# PHOTODIODE.net
KiCad netlist of a schematic drawn in Altium Designer
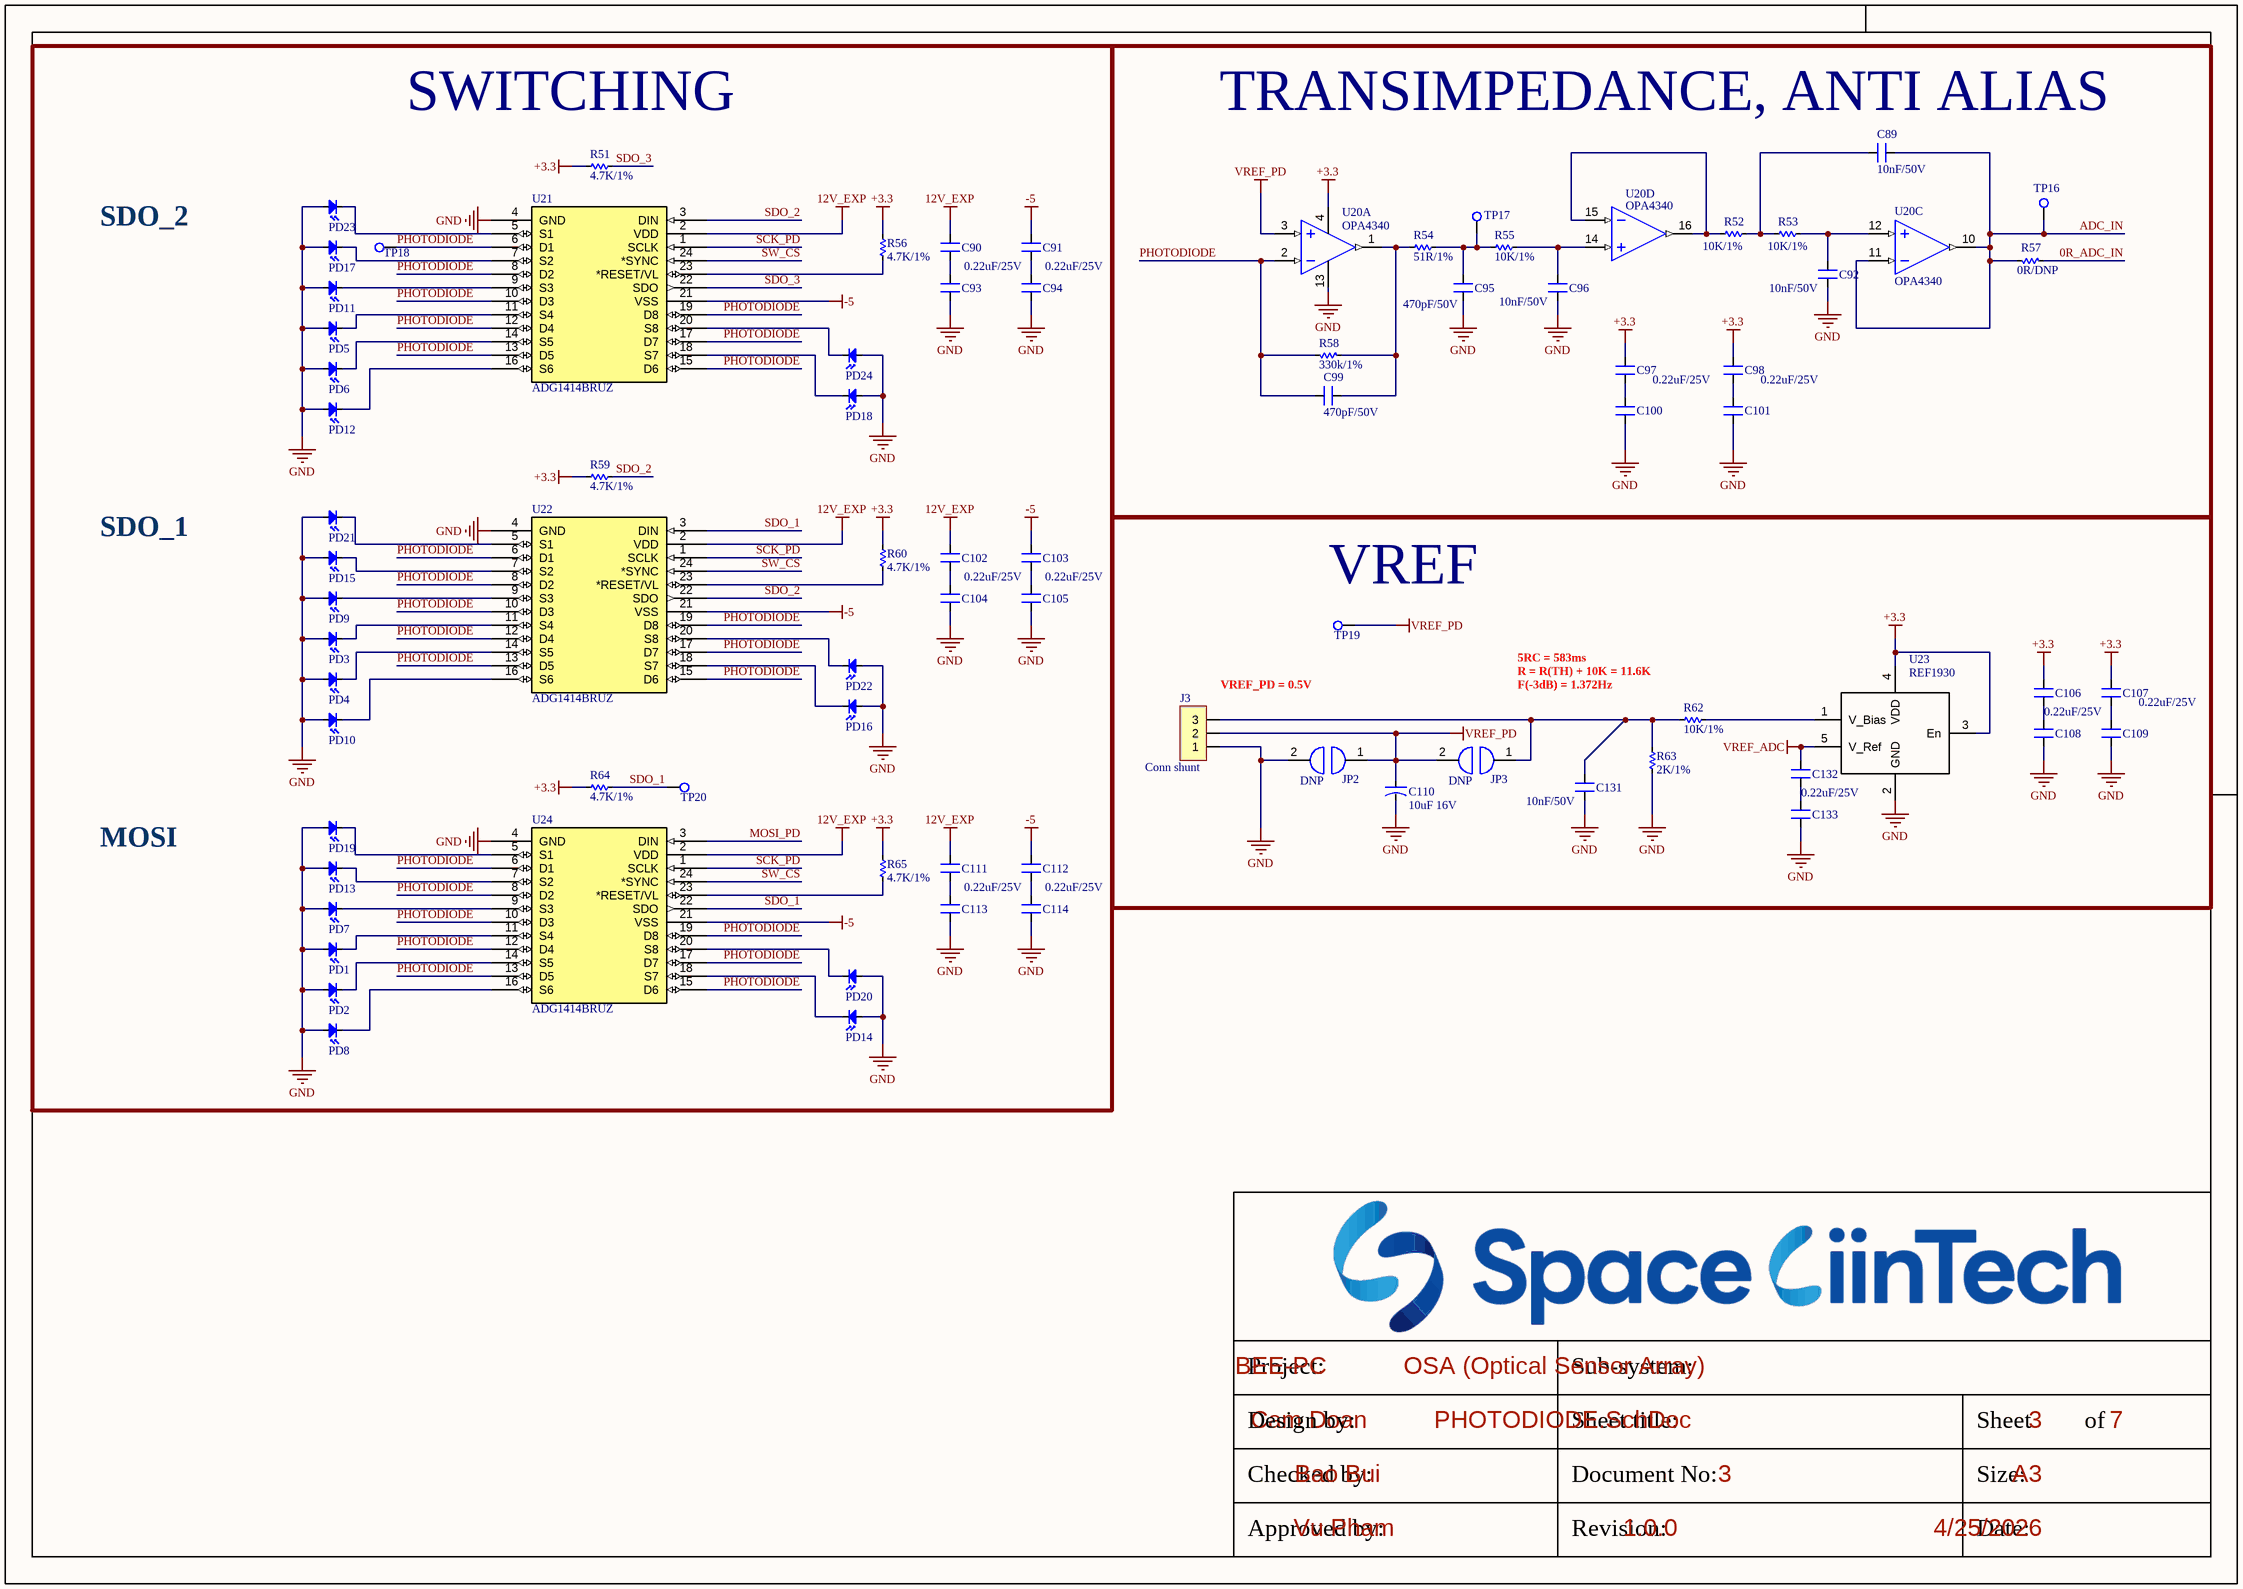
[diagram p0: PHOTODIODE.SchDoc]

(export (version "E")
  (design (tool "Eeschema 10.0.6"))
  (components
    (comp (ref "C89")
      (value "10nF/50V")
      (footprint "CN-SMD-0603")
      (description "CL10B103KB8NNNC")
      (libsource (lib "Capacitors") (part "CM"))
    )
    (comp (ref "C90")
      (value "0.22uF/25V")
      (footprint "CN-SMD-0603")
      (description "CL10B224KA8NNNC")
      (libsource (lib "Capacitors") (part "CM"))
    )
    (comp (ref "C91")
      (value "0.22uF/25V")
      (footprint "CN-SMD-0603")
      (description "CL10B224KA8NNNC")
      (libsource (lib "Capacitors") (part "CM"))
    )
    (comp (ref "C92")
      (value "10nF/50V")
      (footprint "CN-SMD-0603")
      (description "CL10B103KB8NNNC")
      (libsource (lib "Capacitors") (part "CM"))
    )
    (comp (ref "C93")
      (value "0.22uF/25V")
      (footprint "CN-SMD-0603")
      (description "CL10B224KA8NNNC")
      (libsource (lib "Capacitors") (part "CM"))
    )
    (comp (ref "C94")
      (value "0.22uF/25V")
      (footprint "CN-SMD-0603")
      (description "CL10B224KA8NNNC")
      (libsource (lib "Capacitors") (part "CM"))
    )
    (comp (ref "C95")
      (value "470pF/50V")
      (footprint "CN-SMD-0603")
      (description "CL10B471KB8NNNC")
      (libsource (lib "Capacitors") (part "CM"))
    )
    (comp (ref "C96")
      (value "10nF/50V")
      (footprint "CN-SMD-0603")
      (description "CL10B103KB8NNNC")
      (libsource (lib "Capacitors") (part "CM"))
    )
    (comp (ref "C97")
      (value "0.22uF/25V")
      (footprint "CN-SMD-0603")
      (description "CL10B224KA8NNNC")
      (libsource (lib "Capacitors") (part "CM"))
    )
    (comp (ref "C98")
      (value "0.22uF/25V")
      (footprint "CN-SMD-0603")
      (description "CL10B224KA8NNNC")
      (libsource (lib "Capacitors") (part "CM"))
    )
    (comp (ref "C99")
      (value "470pF/50V")
      (footprint "CN-SMD-0603")
      (description "CL10B471KB8NNNC")
      (libsource (lib "Capacitors") (part "CM"))
    )
    (comp (ref "C100")
      (value "0.22uF/25V")
      (footprint "CN-SMD-0603")
      (description "CL10B224KA8NNNC")
      (libsource (lib "Capacitors") (part "CM"))
    )
    (comp (ref "C101")
      (value "0.22uF/25V")
      (footprint "CN-SMD-0603")
      (description "CL10B224KA8NNNC")
      (libsource (lib "Capacitors") (part "CM"))
    )
    (comp (ref "C102")
      (value "0.22uF/25V")
      (footprint "CN-SMD-0603")
      (description "CL10B224KA8NNNC")
      (libsource (lib "Capacitors") (part "CM"))
    )
    (comp (ref "C103")
      (value "0.22uF/25V")
      (footprint "CN-SMD-0603")
      (description "CL10B224KA8NNNC")
      (libsource (lib "Capacitors") (part "CM"))
    )
    (comp (ref "C104")
      (value "0.22uF/25V")
      (footprint "CN-SMD-0603")
      (description "CL10B224KA8NNNC")
      (libsource (lib "Capacitors") (part "CM"))
    )
    (comp (ref "C105")
      (value "0.22uF/25V")
      (footprint "CN-SMD-0603")
      (description "CL10B224KA8NNNC")
      (libsource (lib "Capacitors") (part "CM"))
    )
    (comp (ref "C106")
      (value "0.22uF/25V")
      (footprint "CN-SMD-0603")
      (description "CL10B224KA8NNNC")
      (libsource (lib "Capacitors") (part "CM"))
    )
    (comp (ref "C107")
      (value "0.22uF/25V")
      (footprint "CN-SMD-0603")
      (description "CL10B224KA8NNNC")
      (libsource (lib "Capacitors") (part "CM"))
    )
    (comp (ref "C108")
      (value "0.22uF/25V")
      (footprint "CN-SMD-0603")
      (description "CL10B224KA8NNNC")
      (libsource (lib "Capacitors") (part "CM"))
    )
    (comp (ref "C109")
      (value "0.22uF/25V")
      (footprint "CN-SMD-0603")
      (description "CL10B224KA8NNNC")
      (libsource (lib "Capacitors") (part "CM"))
    )
    (comp (ref "C110")
      (value "10uF 16V")
      (footprint "CAP_TANT_1206")
      (description "TAJA106K016RNJ")
      (fields (field (name "PUBLISHER") "Altium Limited"))
      (libsource (lib "Library_HUNG") (part "CN-ALU-SMD"))
    )
    (comp (ref "C111")
      (value "0.22uF/25V")
      (footprint "CN-SMD-0603")
      (description "CL10B224KA8NNNC")
      (libsource (lib "Capacitors") (part "CM"))
    )
    (comp (ref "C112")
      (value "0.22uF/25V")
      (footprint "CN-SMD-0603")
      (description "CL10B224KA8NNNC")
      (libsource (lib "Capacitors") (part "CM"))
    )
    (comp (ref "C113")
      (value "0.22uF/25V")
      (footprint "CN-SMD-0603")
      (description "CL10B224KA8NNNC")
      (libsource (lib "Capacitors") (part "CM"))
    )
    (comp (ref "C114")
      (value "0.22uF/25V")
      (footprint "CN-SMD-0603")
      (description "CL10B224KA8NNNC")
      (libsource (lib "Capacitors") (part "CM"))
    )
    (comp (ref "C131")
      (value "10nF/50V")
      (footprint "CN-SMD-0603")
      (description "CL10B103KB8NNNC")
      (libsource (lib "Capacitors") (part "CM"))
    )
    (comp (ref "C132")
      (value "0.22uF/25V")
      (footprint "CN-SMD-0603")
      (description "CL10B224KA8NNNC")
      (libsource (lib "Capacitors") (part "CM"))
    )
    (comp (ref "C133")
      (value "0.22uF/25V")
      (footprint "CN-SMD-0603")
      (description "CL10B224KA8NNNC")
      (libsource (lib "Capacitors") (part "CM"))
    )
    (comp (ref "J3")
      (value "Conn shunt")
      (footprint "M50-3930342")
      (description "WR-PHD 2.54 mm Angled Socket Header")
      (fields
        (field (name "MANUFACTURER") "Würth Elektronik eiSos GmbH")
        (field (name "PARTNO") "613003143121")
        (field (name "CREATED BY") "Karrer Zheng")
      )
      (libsource (lib "Library") (part "JP3"))
    )
    (comp (ref "JP2") (value "DNP") (footprint "JUMPER_1608") (libsource (lib "EXP_V1") (part "JUMPER")))
    (comp (ref "JP3") (value "DNP") (footprint "JUMPER_1608") (libsource (lib "EXP_V1") (part "JUMPER")))
    (comp (ref "PD1")
      (value "Photodiode")
      (footprint "VEMD5080X01")
      (description "VEMD5080X01")
      (libsource (lib "Library_HUNG") (part "Photodiode"))
    )
    (comp (ref "PD2")
      (value "Photodiode")
      (footprint "VEMD5080X01")
      (description "VEMD5080X01")
      (libsource (lib "Library_HUNG") (part "Photodiode"))
    )
    (comp (ref "PD3")
      (value "Photodiode")
      (footprint "VEMD5080X01")
      (description "VEMD5080X01")
      (libsource (lib "Library_HUNG") (part "Photodiode"))
    )
    (comp (ref "PD4")
      (value "Photodiode")
      (footprint "VEMD5080X01")
      (description "VEMD5080X01")
      (libsource (lib "Library_HUNG") (part "Photodiode"))
    )
    (comp (ref "PD5")
      (value "Photodiode")
      (footprint "VEMD5080X01")
      (description "VEMD5080X01")
      (libsource (lib "Library_HUNG") (part "Photodiode"))
    )
    (comp (ref "PD6")
      (value "Photodiode")
      (footprint "VEMD5080X01")
      (description "VEMD5080X01")
      (libsource (lib "Library_HUNG") (part "Photodiode"))
    )
    (comp (ref "PD7")
      (value "Photodiode")
      (footprint "VEMD5080X01")
      (description "VEMD5080X01")
      (libsource (lib "Library_HUNG") (part "Photodiode"))
    )
    (comp (ref "PD8")
      (value "Photodiode")
      (footprint "VEMD5080X01")
      (description "VEMD5080X01")
      (libsource (lib "Library_HUNG") (part "Photodiode"))
    )
    (comp (ref "PD9")
      (value "Photodiode")
      (footprint "VEMD5080X01")
      (description "VEMD5080X01")
      (libsource (lib "Library_HUNG") (part "Photodiode"))
    )
    (comp (ref "PD10")
      (value "Photodiode")
      (footprint "VEMD5080X01")
      (description "VEMD5080X01")
      (libsource (lib "Library_HUNG") (part "Photodiode"))
    )
    (comp (ref "PD11")
      (value "Photodiode")
      (footprint "VEMD5080X01")
      (description "VEMD5080X01")
      (libsource (lib "Library_HUNG") (part "Photodiode"))
    )
    (comp (ref "PD12")
      (value "Photodiode")
      (footprint "VEMD5080X01")
      (description "VEMD5080X01")
      (libsource (lib "Library_HUNG") (part "Photodiode"))
    )
    (comp (ref "PD13")
      (value "Photodiode")
      (footprint "VEMD5080X01")
      (description "VEMD5080X01")
      (libsource (lib "Library_HUNG") (part "Photodiode"))
    )
    (comp (ref "PD14")
      (value "Photodiode")
      (footprint "VEMD5080X01")
      (description "VEMD5080X01")
      (libsource (lib "Library_HUNG") (part "Photodiode"))
    )
    (comp (ref "PD15")
      (value "Photodiode")
      (footprint "VEMD5080X01")
      (description "VEMD5080X01")
      (libsource (lib "Library_HUNG") (part "Photodiode"))
    )
    (comp (ref "PD16")
      (value "Photodiode")
      (footprint "VEMD5080X01")
      (description "VEMD5080X01")
      (libsource (lib "Library_HUNG") (part "Photodiode"))
    )
    (comp (ref "PD17")
      (value "Photodiode")
      (footprint "VEMD5080X01")
      (description "VEMD5080X01")
      (libsource (lib "Library_HUNG") (part "Photodiode"))
    )
    (comp (ref "PD18")
      (value "Photodiode")
      (footprint "VEMD5080X01")
      (description "VEMD5080X01")
      (libsource (lib "Library_HUNG") (part "Photodiode"))
    )
    (comp (ref "PD19")
      (value "Photodiode")
      (footprint "VEMD5080X01")
      (description "VEMD5080X01")
      (libsource (lib "Library_HUNG") (part "Photodiode"))
    )
    (comp (ref "PD20")
      (value "Photodiode")
      (footprint "VEMD5080X01")
      (description "VEMD5080X01")
      (libsource (lib "Library_HUNG") (part "Photodiode"))
    )
    (comp (ref "PD21")
      (value "Photodiode")
      (footprint "VEMD5080X01")
      (description "VEMD5080X01")
      (libsource (lib "Library_HUNG") (part "Photodiode"))
    )
    (comp (ref "PD22")
      (value "Photodiode")
      (footprint "VEMD5080X01")
      (description "VEMD5080X01")
      (libsource (lib "Library_HUNG") (part "Photodiode"))
    )
    (comp (ref "PD23")
      (value "Photodiode")
      (footprint "VEMD5080X01")
      (description "VEMD5080X01")
      (libsource (lib "Library_HUNG") (part "Photodiode"))
    )
    (comp (ref "PD24")
      (value "Photodiode")
      (footprint "VEMD5080X01")
      (description "VEMD5080X01")
      (libsource (lib "Library_HUNG") (part "Photodiode"))
    )
    (comp (ref "R51")
      (value "4.7K/1%")
      (footprint "RES-SMD-0603")
      (description "ERJ-3EKF4701V")
      (fields
        (field (name "MANUFACTURER") "Generic Components")
        (field (name "PUBLISHER") "Altium Hobart Technology Centre")
      )
      (libsource (lib "Library") (part "Res-SMD"))
    )
    (comp (ref "R52")
      (value "10K/1%")
      (footprint "RES-SMD-0603")
      (description "ERJ-3EKF1002V")
      (fields
        (field (name "MANUFACTURER") "Generic Components")
        (field (name "PUBLISHER") "Altium Hobart Technology Centre")
      )
      (libsource (lib "Library") (part "Res-SMD"))
    )
    (comp (ref "R53")
      (value "10K/1%")
      (footprint "RES-SMD-0603")
      (description "ERJ-3EKF1002V")
      (fields
        (field (name "MANUFACTURER") "Generic Components")
        (field (name "PUBLISHER") "Altium Hobart Technology Centre")
      )
      (libsource (lib "Library") (part "Res-SMD"))
    )
    (comp (ref "R54")
      (value "51R/1%")
      (footprint "RES-SMD-0603")
      (description "ERJ-3EKF51R0V")
      (fields
        (field (name "MANUFACTURER") "Generic Components")
        (field (name "PUBLISHER") "Altium Hobart Technology Centre")
      )
      (libsource (lib "Library") (part "Res-SMD"))
    )
    (comp (ref "R55")
      (value "10K/1%")
      (footprint "RES-SMD-0603")
      (description "ERJ-3EKF1002V")
      (fields
        (field (name "MANUFACTURER") "Generic Components")
        (field (name "PUBLISHER") "Altium Hobart Technology Centre")
      )
      (libsource (lib "Library") (part "Res-SMD"))
    )
    (comp (ref "R56")
      (value "4.7K/1%")
      (footprint "RES-SMD-0603")
      (description "ERJ-3EKF4701V")
      (fields
        (field (name "MANUFACTURER") "Generic Components")
        (field (name "PUBLISHER") "Altium Hobart Technology Centre")
      )
      (libsource (lib "Library") (part "Res-SMD"))
    )
    (comp (ref "R57")
      (value "0R/DNP")
      (footprint "RES-SMD-0603")
      (description "ERJ-3GEY0R00V")
      (fields
        (field (name "MANUFACTURER") "Generic Components")
        (field (name "PUBLISHER") "Altium Hobart Technology Centre")
      )
      (libsource (lib "Library") (part "Res-SMD"))
    )
    (comp (ref "R58")
      (value "330k/1%")
      (footprint "RES-SMD-0603")
      (description "ERJ-3EKF3303V")
      (fields
        (field (name "MANUFACTURER") "Generic Components")
        (field (name "PUBLISHER") "Altium Hobart Technology Centre")
      )
      (libsource (lib "Library") (part "Res-SMD"))
    )
    (comp (ref "R59")
      (value "4.7K/1%")
      (footprint "RES-SMD-0603")
      (description "ERJ-3EKF4701V")
      (fields
        (field (name "MANUFACTURER") "Generic Components")
        (field (name "PUBLISHER") "Altium Hobart Technology Centre")
      )
      (libsource (lib "Library") (part "Res-SMD"))
    )
    (comp (ref "R60")
      (value "4.7K/1%")
      (footprint "RES-SMD-0603")
      (description "ERJ-3EKF4701V")
      (fields
        (field (name "MANUFACTURER") "Generic Components")
        (field (name "PUBLISHER") "Altium Hobart Technology Centre")
      )
      (libsource (lib "Library") (part "Res-SMD"))
    )
    (comp (ref "R62")
      (value "10K/1%")
      (footprint "RES-SMD-0603")
      (description "ERJ-3EKF1002V")
      (fields
        (field (name "MANUFACTURER") "Generic Components")
        (field (name "PUBLISHER") "Altium Hobart Technology Centre")
      )
      (libsource (lib "Library") (part "Res-SMD"))
    )
    (comp (ref "R63")
      (value "2K/1%")
      (footprint "RES-SMD-0603")
      (description "ERJ-3EKF2001V")
      (fields
        (field (name "MANUFACTURER") "Generic Components")
        (field (name "PUBLISHER") "Altium Hobart Technology Centre")
      )
      (libsource (lib "Library") (part "Res-SMD"))
    )
    (comp (ref "R64")
      (value "4.7K/1%")
      (footprint "RES-SMD-0603")
      (description "ERJ-3EKF4701V")
      (fields
        (field (name "MANUFACTURER") "Generic Components")
        (field (name "PUBLISHER") "Altium Hobart Technology Centre")
      )
      (libsource (lib "Library") (part "Res-SMD"))
    )
    (comp (ref "R65")
      (value "4.7K/1%")
      (footprint "RES-SMD-0603")
      (description "ERJ-3EKF4701V")
      (fields
        (field (name "MANUFACTURER") "Generic Components")
        (field (name "PUBLISHER") "Altium Hobart Technology Centre")
      )
      (libsource (lib "Library") (part "Res-SMD"))
    )
    (comp (ref "TP16")
      (value "Test_Point")
      (footprint "TESTPOINT")
      (libsource (lib "Library_HUNG") (part "Test_Point"))
    )
    (comp (ref "TP17")
      (value "Test_Point")
      (footprint "TESTPOINT")
      (libsource (lib "Library_HUNG") (part "Test_Point"))
    )
    (comp (ref "TP18")
      (value "Test_Point")
      (footprint "TESTPOINT")
      (libsource (lib "Library_HUNG") (part "Test_Point"))
    )
    (comp (ref "TP19")
      (value "Test_Point")
      (footprint "TESTPOINT")
      (libsource (lib "Library_HUNG") (part "Test_Point"))
    )
    (comp (ref "TP20")
      (value "Test_Point")
      (footprint "TESTPOINT")
      (libsource (lib "Library_HUNG") (part "Test_Point"))
    )
    (comp (ref "U20")
      (value "OPA4340")
      (footprint "SSOP16")
      (description "OPA4340UA/2K5")
      (libsource (lib "Library") (part "OPA4340"))
    )
    (comp (ref "U21")
      (value "ADG1414BRUZ")
      (footprint "TSSOP24")
      (libsource (lib "Library_HUNG") (part "ADG1414BRUZ"))
    )
    (comp (ref "U22")
      (value "ADG1414BRUZ")
      (footprint "TSSOP24")
      (libsource (lib "Library_HUNG") (part "ADG1414BRUZ"))
    )
    (comp (ref "U23")
      (value "REF1930")
      (footprint "SOT23-5")
      (description "REF1941AIDDCT")
      (libsource (lib "Library") (part "REF19xx"))
    )
    (comp (ref "U24")
      (value "ADG1414BRUZ")
      (footprint "TSSOP24")
      (libsource (lib "Library_HUNG") (part "ADG1414BRUZ"))
    )
  )
  (nets
    (net (code "1") (name "+3.3") (class "Default")
      (node (ref "C106") (pin "2") (pinfunction "2_2") (pintype "passive"))
      (node (ref "C107") (pin "2") (pinfunction "2_2") (pintype "passive"))
      (node (ref "C97") (pin "2") (pinfunction "2_2") (pintype "passive"))
      (node (ref "C98") (pin "2") (pinfunction "2_2") (pintype "passive"))
      (node (ref "R51") (pin "2") (pinfunction "2_2") (pintype "passive"))
      (node (ref "R56") (pin "2") (pinfunction "2_2") (pintype "passive"))
      (node (ref "R59") (pin "2") (pinfunction "2_2") (pintype "passive"))
      (node (ref "R60") (pin "2") (pinfunction "2_2") (pintype "passive"))
      (node (ref "R64") (pin "2") (pinfunction "2_2") (pintype "passive"))
      (node (ref "R65") (pin "2") (pinfunction "2_2") (pintype "passive"))
      (node (ref "U20") (pin "4") (pinfunction "+V_4") (pintype "passive"))
      (node (ref "U23") (pin "3") (pinfunction "En_3") (pintype "passive"))
      (node (ref "U23") (pin "4") (pinfunction "VDD_4") (pintype "passive"))
    )
    (net (code "2") (name "-5") (class "Default")
      (node (ref "C103") (pin "2") (pinfunction "2_2") (pintype "passive"))
      (node (ref "C112") (pin "2") (pinfunction "2_2") (pintype "passive"))
      (node (ref "C91") (pin "2") (pinfunction "2_2") (pintype "passive"))
      (node (ref "U21") (pin "21") (pinfunction "VSS_21") (pintype "power_in"))
      (node (ref "U22") (pin "21") (pinfunction "VSS_21") (pintype "power_in"))
      (node (ref "U24") (pin "21") (pinfunction "VSS_21") (pintype "power_in"))
    )
    (net (code "3") (name "/0R_ADC_IN") (class "Default")
      (node (ref "R57") (pin "1") (pinfunction "1_1") (pintype "passive"))
    )
    (net (code "4") (name "/ADC_IN") (class "Default")
      (node (ref "C89") (pin "1") (pinfunction "1_1") (pintype "passive"))
      (node (ref "R57") (pin "2") (pinfunction "2_2") (pintype "passive"))
      (node (ref "TP16") (pin "1") (pintype "power_in"))
      (node (ref "U20") (pin "10") (pinfunction "OUT_10") (pintype "output"))
      (node (ref "U20") (pin "11") (pinfunction "IN-_11") (pintype "input"))
    )
    (net (code "5") (name "/MOSI_PD") (class "Default")
      (node (ref "U24") (pin "3") (pinfunction "DIN_3") (pintype "input"))
    )
    (net (code "6") (name "/PHOTODIODE") (class "Default")
      (node (ref "C99") (pin "1") (pinfunction "1_1") (pintype "passive"))
      (node (ref "R58") (pin "1") (pinfunction "1_1") (pintype "passive"))
      (node (ref "TP18") (pin "1") (pintype "power_in"))
      (node (ref "U20") (pin "2") (pinfunction "IN-_2") (pintype "input"))
      (node (ref "U21") (pin "10") (pinfunction "D3_10") (pintype "bidirectional"))
      (node (ref "U21") (pin "12") (pinfunction "D4_12") (pintype "bidirectional"))
      (node (ref "U21") (pin "13") (pinfunction "D5_13") (pintype "bidirectional"))
      (node (ref "U21") (pin "15") (pinfunction "D6_15") (pintype "bidirectional"))
      (node (ref "U21") (pin "17") (pinfunction "D7_17") (pintype "bidirectional"))
      (node (ref "U21") (pin "19") (pinfunction "D8_19") (pintype "bidirectional"))
      (node (ref "U21") (pin "6") (pinfunction "D1_6") (pintype "bidirectional"))
      (node (ref "U21") (pin "8") (pinfunction "D2_8") (pintype "bidirectional"))
      (node (ref "U22") (pin "10") (pinfunction "D3_10") (pintype "bidirectional"))
      (node (ref "U22") (pin "12") (pinfunction "D4_12") (pintype "bidirectional"))
      (node (ref "U22") (pin "13") (pinfunction "D5_13") (pintype "bidirectional"))
      (node (ref "U22") (pin "15") (pinfunction "D6_15") (pintype "bidirectional"))
      (node (ref "U22") (pin "17") (pinfunction "D7_17") (pintype "bidirectional"))
      (node (ref "U22") (pin "19") (pinfunction "D8_19") (pintype "bidirectional"))
      (node (ref "U22") (pin "6") (pinfunction "D1_6") (pintype "bidirectional"))
      (node (ref "U22") (pin "8") (pinfunction "D2_8") (pintype "bidirectional"))
      (node (ref "U24") (pin "10") (pinfunction "D3_10") (pintype "bidirectional"))
      (node (ref "U24") (pin "12") (pinfunction "D4_12") (pintype "bidirectional"))
      (node (ref "U24") (pin "13") (pinfunction "D5_13") (pintype "bidirectional"))
      (node (ref "U24") (pin "15") (pinfunction "D6_15") (pintype "bidirectional"))
      (node (ref "U24") (pin "17") (pinfunction "D7_17") (pintype "bidirectional"))
      (node (ref "U24") (pin "19") (pinfunction "D8_19") (pintype "bidirectional"))
      (node (ref "U24") (pin "6") (pinfunction "D1_6") (pintype "bidirectional"))
      (node (ref "U24") (pin "8") (pinfunction "D2_8") (pintype "bidirectional"))
    )
    (net (code "7") (name "/SCK_PD") (class "Default")
      (node (ref "U21") (pin "1") (pinfunction "SCLK_1") (pintype "input"))
      (node (ref "U22") (pin "1") (pinfunction "SCLK_1") (pintype "input"))
      (node (ref "U24") (pin "1") (pinfunction "SCLK_1") (pintype "input"))
    )
    (net (code "8") (name "/SDO_1") (class "Default")
      (node (ref "R64") (pin "1") (pinfunction "1_1") (pintype "passive"))
      (node (ref "TP20") (pin "1") (pintype "power_in"))
      (node (ref "U22") (pin "3") (pinfunction "DIN_3") (pintype "input"))
      (node (ref "U24") (pin "22") (pinfunction "SDO_22") (pintype "output"))
    )
    (net (code "9") (name "/SDO_2") (class "Default")
      (node (ref "R59") (pin "1") (pinfunction "1_1") (pintype "passive"))
      (node (ref "U21") (pin "3") (pinfunction "DIN_3") (pintype "input"))
      (node (ref "U22") (pin "22") (pinfunction "SDO_22") (pintype "output"))
    )
    (net (code "10") (name "/SDO_3") (class "Default")
      (node (ref "R51") (pin "1") (pinfunction "1_1") (pintype "passive"))
      (node (ref "U21") (pin "22") (pinfunction "SDO_22") (pintype "output"))
    )
    (net (code "11") (name "/SW_CS") (class "Default")
      (node (ref "U21") (pin "24") (pinfunction "*SYNC_24") (pintype "input"))
      (node (ref "U22") (pin "24") (pinfunction "*SYNC_24") (pintype "input"))
      (node (ref "U24") (pin "24") (pinfunction "*SYNC_24") (pintype "input"))
    )
    (net (code "12") (name "12V_EXP") (class "Default")
      (node (ref "C102") (pin "2") (pinfunction "2_2") (pintype "passive"))
      (node (ref "C111") (pin "2") (pinfunction "2_2") (pintype "passive"))
      (node (ref "C90") (pin "2") (pinfunction "2_2") (pintype "passive"))
      (node (ref "U21") (pin "2") (pinfunction "VDD_2") (pintype "power_in"))
      (node (ref "U22") (pin "2") (pinfunction "VDD_2") (pintype "power_in"))
      (node (ref "U24") (pin "2") (pinfunction "VDD_2") (pintype "power_in"))
    )
    (net (code "13") (name "GND") (class "Default")
      (node (ref "C100") (pin "1") (pinfunction "1_1") (pintype "passive"))
      (node (ref "C101") (pin "1") (pinfunction "1_1") (pintype "passive"))
      (node (ref "C104") (pin "1") (pinfunction "1_1") (pintype "passive"))
      (node (ref "C105") (pin "1") (pinfunction "1_1") (pintype "passive"))
      (node (ref "C108") (pin "1") (pinfunction "1_1") (pintype "passive"))
      (node (ref "C109") (pin "1") (pinfunction "1_1") (pintype "passive"))
      (node (ref "C110") (pin "2") (pinfunction "2_2") (pintype "passive"))
      (node (ref "C113") (pin "1") (pinfunction "1_1") (pintype "passive"))
      (node (ref "C114") (pin "1") (pinfunction "1_1") (pintype "passive"))
      (node (ref "C131") (pin "1") (pinfunction "1_1") (pintype "passive"))
      (node (ref "C133") (pin "1") (pinfunction "1_1") (pintype "passive"))
      (node (ref "C92") (pin "1") (pinfunction "1_1") (pintype "passive"))
      (node (ref "C93") (pin "1") (pinfunction "1_1") (pintype "passive"))
      (node (ref "C94") (pin "1") (pinfunction "1_1") (pintype "passive"))
      (node (ref "C95") (pin "1") (pinfunction "1_1") (pintype "passive"))
      (node (ref "C96") (pin "1") (pinfunction "1_1") (pintype "passive"))
      (node (ref "J3") (pin "1") (pinfunction "1_1") (pintype "passive"))
      (node (ref "JP2") (pin "2") (pinfunction "2_2") (pintype "passive"))
      (node (ref "PD1") (pin "1") (pinfunction "A_1") (pintype "passive"))
      (node (ref "PD10") (pin "1") (pinfunction "A_1") (pintype "passive"))
      (node (ref "PD11") (pin "1") (pinfunction "A_1") (pintype "passive"))
      (node (ref "PD12") (pin "1") (pinfunction "A_1") (pintype "passive"))
      (node (ref "PD13") (pin "1") (pinfunction "A_1") (pintype "passive"))
      (node (ref "PD14") (pin "1") (pinfunction "A_1") (pintype "passive"))
      (node (ref "PD15") (pin "1") (pinfunction "A_1") (pintype "passive"))
      (node (ref "PD16") (pin "1") (pinfunction "A_1") (pintype "passive"))
      (node (ref "PD17") (pin "1") (pinfunction "A_1") (pintype "passive"))
      (node (ref "PD18") (pin "1") (pinfunction "A_1") (pintype "passive"))
      (node (ref "PD19") (pin "1") (pinfunction "A_1") (pintype "passive"))
      (node (ref "PD2") (pin "1") (pinfunction "A_1") (pintype "passive"))
      (node (ref "PD20") (pin "1") (pinfunction "A_1") (pintype "passive"))
      (node (ref "PD21") (pin "1") (pinfunction "A_1") (pintype "passive"))
      (node (ref "PD22") (pin "1") (pinfunction "A_1") (pintype "passive"))
      (node (ref "PD23") (pin "1") (pinfunction "A_1") (pintype "passive"))
      (node (ref "PD24") (pin "1") (pinfunction "A_1") (pintype "passive"))
      (node (ref "PD3") (pin "1") (pinfunction "A_1") (pintype "passive"))
      (node (ref "PD4") (pin "1") (pinfunction "A_1") (pintype "passive"))
      (node (ref "PD5") (pin "1") (pinfunction "A_1") (pintype "passive"))
      (node (ref "PD6") (pin "1") (pinfunction "A_1") (pintype "passive"))
      (node (ref "PD7") (pin "1") (pinfunction "A_1") (pintype "passive"))
      (node (ref "PD8") (pin "1") (pinfunction "A_1") (pintype "passive"))
      (node (ref "PD9") (pin "1") (pinfunction "A_1") (pintype "passive"))
      (node (ref "R63") (pin "1") (pinfunction "1_1") (pintype "passive"))
      (node (ref "U20") (pin "13") (pinfunction "-V_13") (pintype "passive"))
      (node (ref "U21") (pin "4") (pinfunction "GND_4") (pintype "power_in"))
      (node (ref "U22") (pin "4") (pinfunction "GND_4") (pintype "power_in"))
      (node (ref "U23") (pin "2") (pinfunction "GND_2") (pintype "passive"))
      (node (ref "U24") (pin "4") (pinfunction "GND_4") (pintype "power_in"))
    )
    (net (code "14") (name "Net-(C89-Pad2)") (class "Default")
      (node (ref "C89") (pin "2") (pinfunction "2_2") (pintype "passive"))
      (node (ref "R52") (pin "2") (pinfunction "2_2") (pintype "passive"))
      (node (ref "R53") (pin "1") (pinfunction "1_1") (pintype "passive"))
    )
    (net (code "15") (name "Net-(C90-Pad1)") (class "Default")
      (node (ref "C90") (pin "1") (pinfunction "1_1") (pintype "passive"))
      (node (ref "C93") (pin "2") (pinfunction "2_2") (pintype "passive"))
    )
    (net (code "16") (name "Net-(C91-Pad1)") (class "Default")
      (node (ref "C91") (pin "1") (pinfunction "1_1") (pintype "passive"))
      (node (ref "C94") (pin "2") (pinfunction "2_2") (pintype "passive"))
    )
    (net (code "17") (name "Net-(C95-Pad2)") (class "Default")
      (node (ref "C95") (pin "2") (pinfunction "2_2") (pintype "passive"))
      (node (ref "R54") (pin "2") (pinfunction "2_2") (pintype "passive"))
      (node (ref "R55") (pin "1") (pinfunction "1_1") (pintype "passive"))
      (node (ref "TP17") (pin "1") (pintype "power_in"))
    )
    (net (code "18") (name "Net-(C100-Pad2)") (class "Default")
      (node (ref "C100") (pin "2") (pinfunction "2_2") (pintype "passive"))
      (node (ref "C97") (pin "1") (pinfunction "1_1") (pintype "passive"))
    )
    (net (code "19") (name "Net-(C101-Pad2)") (class "Default")
      (node (ref "C101") (pin "2") (pinfunction "2_2") (pintype "passive"))
      (node (ref "C98") (pin "1") (pinfunction "1_1") (pintype "passive"))
    )
    (net (code "20") (name "Net-(C102-Pad1)") (class "Default")
      (node (ref "C102") (pin "1") (pinfunction "1_1") (pintype "passive"))
      (node (ref "C104") (pin "2") (pinfunction "2_2") (pintype "passive"))
    )
    (net (code "21") (name "Net-(C103-Pad1)") (class "Default")
      (node (ref "C103") (pin "1") (pinfunction "1_1") (pintype "passive"))
      (node (ref "C105") (pin "2") (pinfunction "2_2") (pintype "passive"))
    )
    (net (code "22") (name "Net-(C106-Pad1)") (class "Default")
      (node (ref "C106") (pin "1") (pinfunction "1_1") (pintype "passive"))
      (node (ref "C108") (pin "2") (pinfunction "2_2") (pintype "passive"))
    )
    (net (code "23") (name "Net-(C107-Pad1)") (class "Default")
      (node (ref "C107") (pin "1") (pinfunction "1_1") (pintype "passive"))
      (node (ref "C109") (pin "2") (pinfunction "2_2") (pintype "passive"))
    )
    (net (code "24") (name "Net-(C111-Pad1)") (class "Default")
      (node (ref "C111") (pin "1") (pinfunction "1_1") (pintype "passive"))
      (node (ref "C113") (pin "2") (pinfunction "2_2") (pintype "passive"))
    )
    (net (code "25") (name "Net-(C112-Pad1)") (class "Default")
      (node (ref "C112") (pin "1") (pinfunction "1_1") (pintype "passive"))
      (node (ref "C114") (pin "2") (pinfunction "2_2") (pintype "passive"))
    )
    (net (code "26") (name "Net-(C131-Pad2)") (class "Default")
      (node (ref "C131") (pin "2") (pinfunction "2_2") (pintype "passive"))
      (node (ref "J3") (pin "3") (pinfunction "3_3") (pintype "passive"))
      (node (ref "JP3") (pin "1") (pinfunction "1_1") (pintype "passive"))
      (node (ref "R62") (pin "2") (pinfunction "2_2") (pintype "passive"))
      (node (ref "R63") (pin "2") (pinfunction "2_2") (pintype "passive"))
    )
    (net (code "27") (name "Net-(C132-Pad1)") (class "Default")
      (node (ref "C132") (pin "1") (pinfunction "1_1") (pintype "passive"))
      (node (ref "C133") (pin "2") (pinfunction "2_2") (pintype "passive"))
    )
    (net (code "28") (name "Net-(PD1-K)") (class "Default")
      (node (ref "PD1") (pin "2") (pinfunction "K_2") (pintype "passive"))
      (node (ref "U24") (pin "11") (pinfunction "S4_11") (pintype "bidirectional"))
    )
    (net (code "29") (name "Net-(PD2-K)") (class "Default")
      (node (ref "PD2") (pin "2") (pinfunction "K_2") (pintype "passive"))
      (node (ref "U24") (pin "14") (pinfunction "S5_14") (pintype "bidirectional"))
    )
    (net (code "30") (name "Net-(PD3-K)") (class "Default")
      (node (ref "PD3") (pin "2") (pinfunction "K_2") (pintype "passive"))
      (node (ref "U22") (pin "11") (pinfunction "S4_11") (pintype "bidirectional"))
    )
    (net (code "31") (name "Net-(PD4-K)") (class "Default")
      (node (ref "PD4") (pin "2") (pinfunction "K_2") (pintype "passive"))
      (node (ref "U22") (pin "14") (pinfunction "S5_14") (pintype "bidirectional"))
    )
    (net (code "32") (name "Net-(PD5-K)") (class "Default")
      (node (ref "PD5") (pin "2") (pinfunction "K_2") (pintype "passive"))
      (node (ref "U21") (pin "11") (pinfunction "S4_11") (pintype "bidirectional"))
    )
    (net (code "33") (name "Net-(PD6-K)") (class "Default")
      (node (ref "PD6") (pin "2") (pinfunction "K_2") (pintype "passive"))
      (node (ref "U21") (pin "14") (pinfunction "S5_14") (pintype "bidirectional"))
    )
    (net (code "34") (name "Net-(PD7-K)") (class "Default")
      (node (ref "PD7") (pin "2") (pinfunction "K_2") (pintype "passive"))
      (node (ref "U24") (pin "9") (pinfunction "S3_9") (pintype "bidirectional"))
    )
    (net (code "35") (name "Net-(PD8-K)") (class "Default")
      (node (ref "PD8") (pin "2") (pinfunction "K_2") (pintype "passive"))
      (node (ref "U24") (pin "16") (pinfunction "S6_16") (pintype "bidirectional"))
    )
    (net (code "36") (name "Net-(PD9-K)") (class "Default")
      (node (ref "PD9") (pin "2") (pinfunction "K_2") (pintype "passive"))
      (node (ref "U22") (pin "9") (pinfunction "S3_9") (pintype "bidirectional"))
    )
    (net (code "37") (name "Net-(PD10-K)") (class "Default")
      (node (ref "PD10") (pin "2") (pinfunction "K_2") (pintype "passive"))
      (node (ref "U22") (pin "16") (pinfunction "S6_16") (pintype "bidirectional"))
    )
    (net (code "38") (name "Net-(PD11-K)") (class "Default")
      (node (ref "PD11") (pin "2") (pinfunction "K_2") (pintype "passive"))
      (node (ref "U21") (pin "9") (pinfunction "S3_9") (pintype "bidirectional"))
    )
    (net (code "39") (name "Net-(PD12-K)") (class "Default")
      (node (ref "PD12") (pin "2") (pinfunction "K_2") (pintype "passive"))
      (node (ref "U21") (pin "16") (pinfunction "S6_16") (pintype "bidirectional"))
    )
    (net (code "40") (name "Net-(PD13-K)") (class "Default")
      (node (ref "PD13") (pin "2") (pinfunction "K_2") (pintype "passive"))
      (node (ref "U24") (pin "7") (pinfunction "S2_7") (pintype "bidirectional"))
    )
    (net (code "41") (name "Net-(PD14-K)") (class "Default")
      (node (ref "PD14") (pin "2") (pinfunction "K_2") (pintype "passive"))
      (node (ref "U24") (pin "18") (pinfunction "S7_18") (pintype "bidirectional"))
    )
    (net (code "42") (name "Net-(PD15-K)") (class "Default")
      (node (ref "PD15") (pin "2") (pinfunction "K_2") (pintype "passive"))
      (node (ref "U22") (pin "7") (pinfunction "S2_7") (pintype "bidirectional"))
    )
    (net (code "43") (name "Net-(PD16-K)") (class "Default")
      (node (ref "PD16") (pin "2") (pinfunction "K_2") (pintype "passive"))
      (node (ref "U22") (pin "18") (pinfunction "S7_18") (pintype "bidirectional"))
    )
    (net (code "44") (name "Net-(PD17-K)") (class "Default")
      (node (ref "PD17") (pin "2") (pinfunction "K_2") (pintype "passive"))
      (node (ref "U21") (pin "7") (pinfunction "S2_7") (pintype "bidirectional"))
    )
    (net (code "45") (name "Net-(PD18-K)") (class "Default")
      (node (ref "PD18") (pin "2") (pinfunction "K_2") (pintype "passive"))
      (node (ref "U21") (pin "18") (pinfunction "S7_18") (pintype "bidirectional"))
    )
    (net (code "46") (name "Net-(PD19-K)") (class "Default")
      (node (ref "PD19") (pin "2") (pinfunction "K_2") (pintype "passive"))
      (node (ref "U24") (pin "5") (pinfunction "S1_5") (pintype "bidirectional"))
    )
    (net (code "47") (name "Net-(PD20-K)") (class "Default")
      (node (ref "PD20") (pin "2") (pinfunction "K_2") (pintype "passive"))
      (node (ref "U24") (pin "20") (pinfunction "S8_20") (pintype "bidirectional"))
    )
    (net (code "48") (name "Net-(PD21-K)") (class "Default")
      (node (ref "PD21") (pin "2") (pinfunction "K_2") (pintype "passive"))
      (node (ref "U22") (pin "5") (pinfunction "S1_5") (pintype "bidirectional"))
    )
    (net (code "49") (name "Net-(PD22-K)") (class "Default")
      (node (ref "PD22") (pin "2") (pinfunction "K_2") (pintype "passive"))
      (node (ref "U22") (pin "20") (pinfunction "S8_20") (pintype "bidirectional"))
    )
    (net (code "50") (name "Net-(PD23-K)") (class "Default")
      (node (ref "PD23") (pin "2") (pinfunction "K_2") (pintype "passive"))
      (node (ref "U21") (pin "5") (pinfunction "S1_5") (pintype "bidirectional"))
    )
    (net (code "51") (name "Net-(PD24-K)") (class "Default")
      (node (ref "PD24") (pin "2") (pinfunction "K_2") (pintype "passive"))
      (node (ref "U21") (pin "20") (pinfunction "S8_20") (pintype "bidirectional"))
    )
    (net (code "52") (name "Net-(U20A-OUT)") (class "Default")
      (node (ref "C99") (pin "2") (pinfunction "2_2") (pintype "passive"))
      (node (ref "R54") (pin "1") (pinfunction "1_1") (pintype "passive"))
      (node (ref "R58") (pin "2") (pinfunction "2_2") (pintype "passive"))
      (node (ref "U20") (pin "1") (pinfunction "OUT_1") (pintype "output"))
    )
    (net (code "53") (name "Net-(U20C-IN+)") (class "Default")
      (node (ref "C92") (pin "2") (pinfunction "2_2") (pintype "passive"))
      (node (ref "R53") (pin "2") (pinfunction "2_2") (pintype "passive"))
      (node (ref "U20") (pin "12") (pinfunction "IN+_12") (pintype "input"))
    )
    (net (code "54") (name "Net-(U20D-IN+)") (class "Default")
      (node (ref "C96") (pin "2") (pinfunction "2_2") (pintype "passive"))
      (node (ref "R55") (pin "2") (pinfunction "2_2") (pintype "passive"))
      (node (ref "U20") (pin "14") (pinfunction "IN+_14") (pintype "input"))
    )
    (net (code "55") (name "Net-(U20D-IN-)") (class "Default")
      (node (ref "R52") (pin "1") (pinfunction "1_1") (pintype "passive"))
      (node (ref "U20") (pin "15") (pinfunction "IN-_15") (pintype "input"))
      (node (ref "U20") (pin "16") (pinfunction "OUT_16") (pintype "output"))
    )
    (net (code "56") (name "Net-(U21-*RESET{slash}VL)") (class "Default")
      (node (ref "R56") (pin "1") (pinfunction "1_1") (pintype "passive"))
      (node (ref "U21") (pin "23") (pinfunction "*RESET/VL_23") (pintype "bidirectional"))
    )
    (net (code "57") (name "Net-(U22-*RESET{slash}VL)") (class "Default")
      (node (ref "R60") (pin "1") (pinfunction "1_1") (pintype "passive"))
      (node (ref "U22") (pin "23") (pinfunction "*RESET/VL_23") (pintype "bidirectional"))
    )
    (net (code "58") (name "Net-(U23-V_Bias)") (class "Default")
      (node (ref "R62") (pin "1") (pinfunction "1_1") (pintype "passive"))
      (node (ref "U23") (pin "1") (pinfunction "V_Bias_1") (pintype "passive"))
    )
    (net (code "59") (name "Net-(U24-*RESET{slash}VL)") (class "Default")
      (node (ref "R65") (pin "1") (pinfunction "1_1") (pintype "passive"))
      (node (ref "U24") (pin "23") (pinfunction "*RESET/VL_23") (pintype "bidirectional"))
    )
    (net (code "60") (name "VREF_ADC") (class "Default")
      (node (ref "C132") (pin "2") (pinfunction "2_2") (pintype "passive"))
      (node (ref "U23") (pin "5") (pinfunction "V_Ref_5") (pintype "passive"))
    )
    (net (code "61") (name "VREF_PD") (class "Default")
      (node (ref "C110") (pin "1") (pinfunction "1_1") (pintype "passive"))
      (node (ref "J3") (pin "2") (pinfunction "2_2") (pintype "passive"))
      (node (ref "JP2") (pin "1") (pinfunction "1_1") (pintype "passive"))
      (node (ref "JP3") (pin "2") (pinfunction "2_2") (pintype "passive"))
      (node (ref "TP19") (pin "1") (pintype "power_in"))
      (node (ref "U20") (pin "3") (pinfunction "IN+_3") (pintype "input"))
    )
  )
)
